# FPGA_misc.net
KiCad netlist of a schematic drawn in Altium Designer
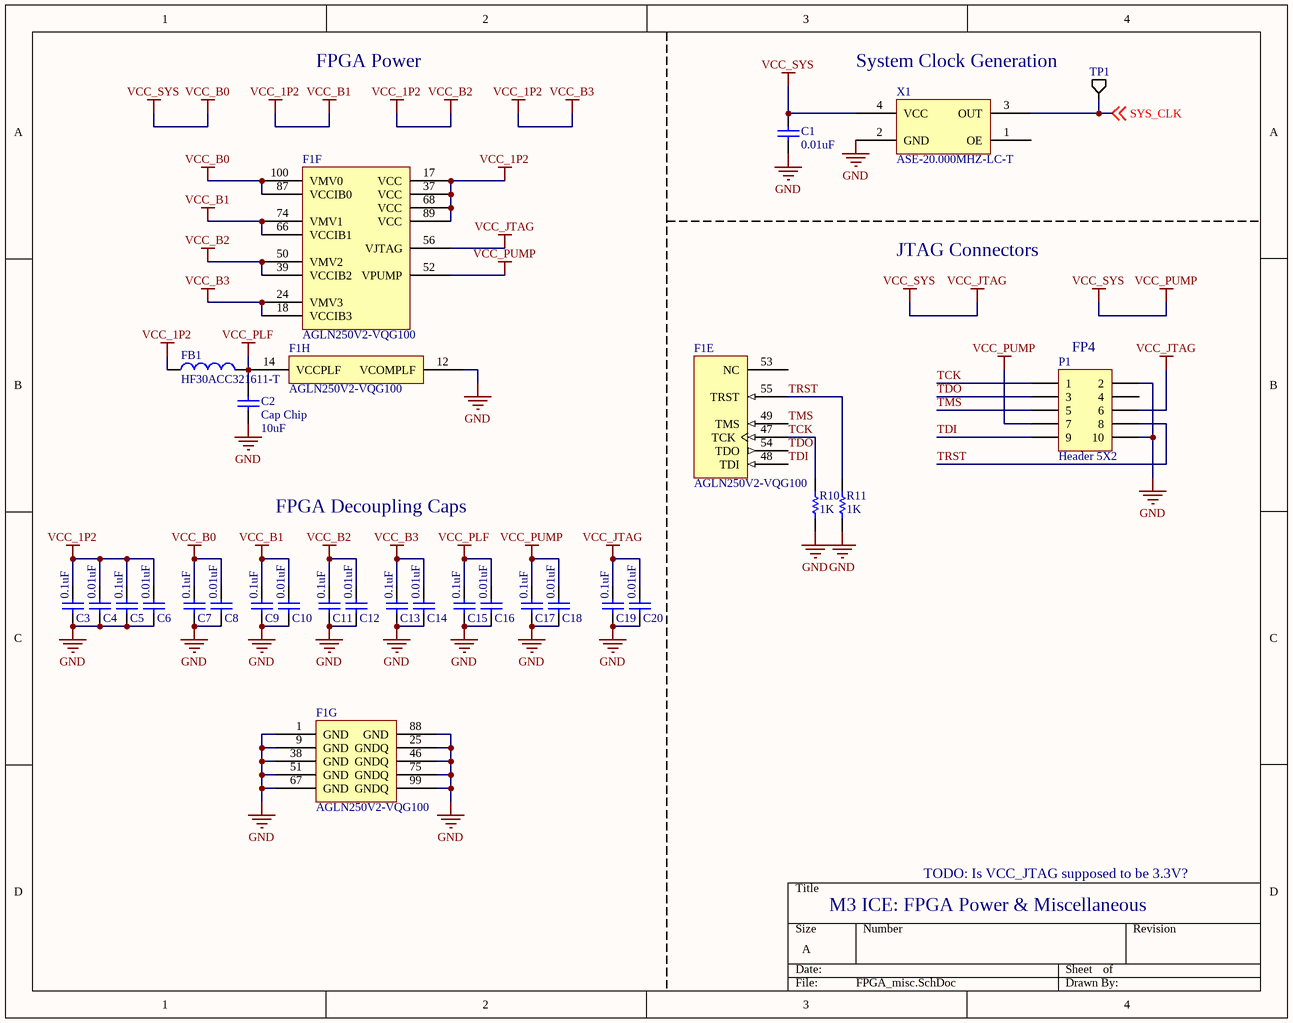
[diagram p0: FPGA_misc.SchDoc]

(export (version "E")
  (design (tool "Eeschema 10.0.6"))
  (components
    (comp (ref "C1")
      (value "0.01uF")
      (footprint "1608[0603]")
      (description "Capacitor (Semiconductor SIM Model)")
      (fields (field (name "Comment") "Cap Semi") (field (name "PUBLISHER") "Altium Limited"))
      (libsource (lib "Miscellaneous Devices") (part "Cap Semi"))
    )
    (comp (ref "C2")
      (value "Cap Chip")
      (footprint "0805")
      (description "Capacitor (Semiconductor SIM Model)")
      (fields (field (name "ALTIUM_VALUE") "10uF") (field (name "PUBLISHER") "Altium Limited"))
      (libsource (lib "M3") (part "Cap Chip"))
    )
    (comp (ref "C3")
      (value "0.1uF")
      (footprint "1608[0603]")
      (description "Capacitor (Semiconductor SIM Model)")
      (fields (field (name "Comment") "Cap Semi") (field (name "PUBLISHER") "Altium Limited"))
      (libsource (lib "Miscellaneous Devices") (part "Cap Semi"))
    )
    (comp (ref "C4")
      (value "0.01uF")
      (footprint "1608[0603]")
      (description "Capacitor (Semiconductor SIM Model)")
      (fields (field (name "Comment") "Cap Semi") (field (name "PUBLISHER") "Altium Limited"))
      (libsource (lib "Miscellaneous Devices") (part "Cap Semi"))
    )
    (comp (ref "C5")
      (value "0.1uF")
      (footprint "1608[0603]")
      (description "Capacitor (Semiconductor SIM Model)")
      (fields (field (name "Comment") "Cap Semi") (field (name "PUBLISHER") "Altium Limited"))
      (libsource (lib "Miscellaneous Devices") (part "Cap Semi"))
    )
    (comp (ref "C6")
      (value "0.01uF")
      (footprint "1608[0603]")
      (description "Capacitor (Semiconductor SIM Model)")
      (fields (field (name "Comment") "Cap Semi") (field (name "PUBLISHER") "Altium Limited"))
      (libsource (lib "Miscellaneous Devices") (part "Cap Semi"))
    )
    (comp (ref "C7")
      (value "0.1uF")
      (footprint "1608[0603]")
      (description "Capacitor (Semiconductor SIM Model)")
      (fields (field (name "Comment") "Cap Semi") (field (name "PUBLISHER") "Altium Limited"))
      (libsource (lib "Miscellaneous Devices") (part "Cap Semi"))
    )
    (comp (ref "C8")
      (value "0.01uF")
      (footprint "1608[0603]")
      (description "Capacitor (Semiconductor SIM Model)")
      (fields (field (name "Comment") "Cap Semi") (field (name "PUBLISHER") "Altium Limited"))
      (libsource (lib "Miscellaneous Devices") (part "Cap Semi"))
    )
    (comp (ref "C9")
      (value "0.1uF")
      (footprint "1608[0603]")
      (description "Capacitor (Semiconductor SIM Model)")
      (fields (field (name "Comment") "Cap Semi") (field (name "PUBLISHER") "Altium Limited"))
      (libsource (lib "Miscellaneous Devices") (part "Cap Semi"))
    )
    (comp (ref "C10")
      (value "0.01uF")
      (footprint "1608[0603]")
      (description "Capacitor (Semiconductor SIM Model)")
      (fields (field (name "Comment") "Cap Semi") (field (name "PUBLISHER") "Altium Limited"))
      (libsource (lib "Miscellaneous Devices") (part "Cap Semi"))
    )
    (comp (ref "C11")
      (value "0.1uF")
      (footprint "1608[0603]")
      (description "Capacitor (Semiconductor SIM Model)")
      (fields (field (name "Comment") "Cap Semi") (field (name "PUBLISHER") "Altium Limited"))
      (libsource (lib "Miscellaneous Devices") (part "Cap Semi"))
    )
    (comp (ref "C12")
      (value "0.01uF")
      (footprint "1608[0603]")
      (description "Capacitor (Semiconductor SIM Model)")
      (fields (field (name "Comment") "Cap Semi") (field (name "PUBLISHER") "Altium Limited"))
      (libsource (lib "Miscellaneous Devices") (part "Cap Semi"))
    )
    (comp (ref "C13")
      (value "0.1uF")
      (footprint "1608[0603]")
      (description "Capacitor (Semiconductor SIM Model)")
      (fields (field (name "Comment") "Cap Semi") (field (name "PUBLISHER") "Altium Limited"))
      (libsource (lib "Miscellaneous Devices") (part "Cap Semi"))
    )
    (comp (ref "C14")
      (value "0.01uF")
      (footprint "1608[0603]")
      (description "Capacitor (Semiconductor SIM Model)")
      (fields (field (name "Comment") "Cap Semi") (field (name "PUBLISHER") "Altium Limited"))
      (libsource (lib "Miscellaneous Devices") (part "Cap Semi"))
    )
    (comp (ref "C15")
      (value "0.1uF")
      (footprint "1608[0603]")
      (description "Capacitor (Semiconductor SIM Model)")
      (fields (field (name "Comment") "Cap Semi") (field (name "PUBLISHER") "Altium Limited"))
      (libsource (lib "Miscellaneous Devices") (part "Cap Semi"))
    )
    (comp (ref "C16")
      (value "0.01uF")
      (footprint "1608[0603]")
      (description "Capacitor (Semiconductor SIM Model)")
      (fields (field (name "Comment") "Cap Semi") (field (name "PUBLISHER") "Altium Limited"))
      (libsource (lib "Miscellaneous Devices") (part "Cap Semi"))
    )
    (comp (ref "C17")
      (value "0.1uF")
      (footprint "1608[0603]")
      (description "Capacitor (Semiconductor SIM Model)")
      (fields (field (name "Comment") "Cap Semi") (field (name "PUBLISHER") "Altium Limited"))
      (libsource (lib "Miscellaneous Devices") (part "Cap Semi"))
    )
    (comp (ref "C18")
      (value "0.01uF")
      (footprint "1608[0603]")
      (description "Capacitor (Semiconductor SIM Model)")
      (fields (field (name "Comment") "Cap Semi") (field (name "PUBLISHER") "Altium Limited"))
      (libsource (lib "Miscellaneous Devices") (part "Cap Semi"))
    )
    (comp (ref "C19")
      (value "0.1uF")
      (footprint "1608[0603]")
      (description "Capacitor (Semiconductor SIM Model)")
      (fields (field (name "Comment") "Cap Semi") (field (name "PUBLISHER") "Altium Limited"))
      (libsource (lib "Miscellaneous Devices") (part "Cap Semi"))
    )
    (comp (ref "C20")
      (value "0.01uF")
      (footprint "1608[0603]")
      (description "Capacitor (Semiconductor SIM Model)")
      (fields (field (name "Comment") "Cap Semi") (field (name "PUBLISHER") "Altium Limited"))
      (libsource (lib "Miscellaneous Devices") (part "Cap Semi"))
    )
    (comp (ref "F1")
      (value "AGLN250V2-VQG100")
      (footprint "VQ100_N")
      (fields (field (name "PUBLISHER") "Altium Limited"))
      (libsource (lib "Actel IGLOO nano") (part "AGLN250V2-VQG100"))
    )
    (comp (ref "FB1")
      (value "HF30ACC321611-T")
      (footprint "Ferrite_Bead_3.2mm_1.6mm")
      (libsource (lib "M3") (part "Ferrite Bead HF30ACC321611-T"))
    )
    (comp (ref "P1")
      (value "Header 5X2")
      (footprint "HDR2X5")
      (description "Header, 5-Pin, Dual row")
      (fields (field (name "PUBLISHER") "Altium Limited"))
      (libsource (lib "Miscellaneous Connectors") (part "Header 5X2"))
    )
    (comp (ref "R10")
      (value "1K")
      (footprint "0603")
      (description "Semiconductor Resistor")
      (fields (field (name "Comment") "Res Chip") (field (name "PUBLISHER") "Altium Limited"))
      (libsource (lib "M3") (part "Res Chip"))
    )
    (comp (ref "R11")
      (value "1K")
      (footprint "0603")
      (description "Semiconductor Resistor")
      (fields (field (name "Comment") "Res Chip") (field (name "PUBLISHER") "Altium Limited"))
      (libsource (lib "M3") (part "Res Chip"))
    )
    (comp (ref "TP1") (value "TP") (footprint "TP") (libsource (lib "M3") (part "TP")))
    (comp (ref "X1")
      (value "ASE-20.000MHZ-LC-T")
      (footprint "CRYSTAL_3.2mm_2.5mm")
      (libsource (lib "M3") (part "ASE-20.000MHZ-LC-T"))
    )
  )
  (nets
    (net (code "1") (name "/TCK") (class "Default")
      (node (ref "F1") (pin "47") (pinfunction "TCK_47") (pintype "input"))
      (node (ref "P1") (pin "1") (pinfunction "1_1") (pintype "passive"))
      (node (ref "R10") (pin "1") (pinfunction "1_1") (pintype "passive"))
    )
    (net (code "2") (name "/TDI") (class "Default")
      (node (ref "F1") (pin "48") (pinfunction "TDI_48") (pintype "input"))
      (node (ref "P1") (pin "9") (pinfunction "9_9") (pintype "passive"))
    )
    (net (code "3") (name "/TDO") (class "Default")
      (node (ref "F1") (pin "54") (pinfunction "TDO_54") (pintype "output"))
      (node (ref "P1") (pin "3") (pinfunction "3_3") (pintype "passive"))
    )
    (net (code "4") (name "/TMS") (class "Default")
      (node (ref "F1") (pin "49") (pinfunction "TMS_49") (pintype "input"))
      (node (ref "P1") (pin "5") (pinfunction "5_5") (pintype "passive"))
    )
    (net (code "5") (name "/TRST") (class "Default")
      (node (ref "F1") (pin "55") (pinfunction "TRST_55") (pintype "input"))
      (node (ref "P1") (pin "8") (pinfunction "8_8") (pintype "passive"))
      (node (ref "R11") (pin "1") (pinfunction "1_1") (pintype "passive"))
    )
    (net (code "6") (name "GND") (class "Default")
      (node (ref "C1") (pin "1") (pinfunction "1_1") (pintype "passive"))
      (node (ref "C10") (pin "1") (pinfunction "1_1") (pintype "passive"))
      (node (ref "C11") (pin "1") (pinfunction "1_1") (pintype "passive"))
      (node (ref "C12") (pin "1") (pinfunction "1_1") (pintype "passive"))
      (node (ref "C13") (pin "1") (pinfunction "1_1") (pintype "passive"))
      (node (ref "C14") (pin "1") (pinfunction "1_1") (pintype "passive"))
      (node (ref "C15") (pin "1") (pinfunction "1_1") (pintype "passive"))
      (node (ref "C16") (pin "1") (pinfunction "1_1") (pintype "passive"))
      (node (ref "C17") (pin "1") (pinfunction "1_1") (pintype "passive"))
      (node (ref "C18") (pin "1") (pinfunction "1_1") (pintype "passive"))
      (node (ref "C19") (pin "1") (pinfunction "1_1") (pintype "passive"))
      (node (ref "C2") (pin "1") (pinfunction "1_1") (pintype "passive"))
      (node (ref "C20") (pin "1") (pinfunction "1_1") (pintype "passive"))
      (node (ref "C3") (pin "1") (pinfunction "1_1") (pintype "passive"))
      (node (ref "C4") (pin "1") (pinfunction "1_1") (pintype "passive"))
      (node (ref "C5") (pin "1") (pinfunction "1_1") (pintype "passive"))
      (node (ref "C6") (pin "1") (pinfunction "1_1") (pintype "passive"))
      (node (ref "C7") (pin "1") (pinfunction "1_1") (pintype "passive"))
      (node (ref "C8") (pin "1") (pinfunction "1_1") (pintype "passive"))
      (node (ref "C9") (pin "1") (pinfunction "1_1") (pintype "passive"))
      (node (ref "F1") (pin "1") (pinfunction "GND_1") (pintype "power_in"))
      (node (ref "F1") (pin "12") (pinfunction "VCOMPLF_12") (pintype "power_in"))
      (node (ref "F1") (pin "25") (pinfunction "GNDQ_25") (pintype "power_in"))
      (node (ref "F1") (pin "38") (pinfunction "GND_38") (pintype "power_in"))
      (node (ref "F1") (pin "46") (pinfunction "GNDQ_46") (pintype "power_in"))
      (node (ref "F1") (pin "51") (pinfunction "GND_51") (pintype "power_in"))
      (node (ref "F1") (pin "67") (pinfunction "GND_67") (pintype "power_in"))
      (node (ref "F1") (pin "75") (pinfunction "GNDQ_75") (pintype "power_in"))
      (node (ref "F1") (pin "88") (pinfunction "GND_88") (pintype "power_in"))
      (node (ref "F1") (pin "9") (pinfunction "GND_9") (pintype "power_in"))
      (node (ref "F1") (pin "99") (pinfunction "GNDQ_99") (pintype "power_in"))
      (node (ref "P1") (pin "10") (pinfunction "10_10") (pintype "passive"))
      (node (ref "P1") (pin "2") (pinfunction "2_2") (pintype "passive"))
      (node (ref "R10") (pin "2") (pinfunction "2_2") (pintype "passive"))
      (node (ref "R11") (pin "2") (pinfunction "2_2") (pintype "passive"))
      (node (ref "X1") (pin "2") (pinfunction "GND_2") (pintype "passive"))
    )
    (net (code "7") (name "SYS_CLK") (class "Default")
      (node (ref "TP1") (pin "1") (pinfunction "A_1") (pintype "passive"))
      (node (ref "X1") (pin "3") (pinfunction "OUT_3") (pintype "passive"))
    )
    (net (code "8") (name "VCC_1P2") (class "Default")
      (node (ref "C10") (pin "2") (pinfunction "2_2") (pintype "passive"))
      (node (ref "C11") (pin "2") (pinfunction "2_2") (pintype "passive"))
      (node (ref "C12") (pin "2") (pinfunction "2_2") (pintype "passive"))
      (node (ref "C13") (pin "2") (pinfunction "2_2") (pintype "passive"))
      (node (ref "C14") (pin "2") (pinfunction "2_2") (pintype "passive"))
      (node (ref "C3") (pin "2") (pinfunction "2_2") (pintype "passive"))
      (node (ref "C4") (pin "2") (pinfunction "2_2") (pintype "passive"))
      (node (ref "C5") (pin "2") (pinfunction "2_2") (pintype "passive"))
      (node (ref "C6") (pin "2") (pinfunction "2_2") (pintype "passive"))
      (node (ref "C9") (pin "2") (pinfunction "2_2") (pintype "passive"))
      (node (ref "F1") (pin "17") (pinfunction "VCC_17") (pintype "power_in"))
      (node (ref "F1") (pin "18") (pinfunction "VCCIB3_18") (pintype "power_in"))
      (node (ref "F1") (pin "24") (pinfunction "VMV3_24") (pintype "power_in"))
      (node (ref "F1") (pin "37") (pinfunction "VCC_37") (pintype "power_in"))
      (node (ref "F1") (pin "39") (pinfunction "VCCIB2_39") (pintype "power_in"))
      (node (ref "F1") (pin "50") (pinfunction "VMV2_50") (pintype "power_in"))
      (node (ref "F1") (pin "66") (pinfunction "VCCIB1_66") (pintype "power_in"))
      (node (ref "F1") (pin "68") (pinfunction "VCC_68") (pintype "power_in"))
      (node (ref "F1") (pin "74") (pinfunction "VMV1_74") (pintype "power_in"))
      (node (ref "F1") (pin "89") (pinfunction "VCC_89") (pintype "power_in"))
      (node (ref "FB1") (pin "1") (pinfunction "1_1") (pintype "passive"))
    )
    (net (code "9") (name "VCC_B0") (class "Default")
      (node (ref "C1") (pin "2") (pinfunction "2_2") (pintype "passive"))
      (node (ref "C17") (pin "2") (pinfunction "2_2") (pintype "passive"))
      (node (ref "C18") (pin "2") (pinfunction "2_2") (pintype "passive"))
      (node (ref "C19") (pin "2") (pinfunction "2_2") (pintype "passive"))
      (node (ref "C20") (pin "2") (pinfunction "2_2") (pintype "passive"))
      (node (ref "C7") (pin "2") (pinfunction "2_2") (pintype "passive"))
      (node (ref "C8") (pin "2") (pinfunction "2_2") (pintype "passive"))
      (node (ref "F1") (pin "100") (pinfunction "VMV0_100") (pintype "power_in"))
      (node (ref "F1") (pin "52") (pinfunction "VPUMP_52") (pintype "power_in"))
      (node (ref "F1") (pin "56") (pinfunction "VJTAG_56") (pintype "power_in"))
      (node (ref "F1") (pin "87") (pinfunction "VCCIB0_87") (pintype "power_in"))
      (node (ref "P1") (pin "6") (pinfunction "6_6") (pintype "passive"))
      (node (ref "P1") (pin "7") (pinfunction "7_7") (pintype "passive"))
      (node (ref "X1") (pin "4") (pinfunction "VCC_4") (pintype "passive"))
    )
    (net (code "10") (name "VCC_PLF") (class "Default")
      (node (ref "C15") (pin "2") (pinfunction "2_2") (pintype "passive"))
      (node (ref "C16") (pin "2") (pinfunction "2_2") (pintype "passive"))
      (node (ref "C2") (pin "2") (pinfunction "2_2") (pintype "passive"))
      (node (ref "F1") (pin "14") (pinfunction "VCCPLF_14") (pintype "power_in"))
      (node (ref "FB1") (pin "2") (pinfunction "2_2") (pintype "passive"))
    )
    (net (code "11") (name "unconnected-(F1E-NC-Pad53)") (class "Default")
      (node (ref "F1") (pin "53") (pinfunction "NC_53") (pintype "passive"))
    )
    (net (code "12") (name "unconnected-(P1-Pad4)") (class "Default")
      (node (ref "P1") (pin "4") (pinfunction "4_4") (pintype "passive"))
    )
    (net (code "13") (name "unconnected-(X1-OE-Pad1)") (class "Default")
      (node (ref "X1") (pin "1") (pinfunction "OE_1") (pintype "passive"))
    )
  )
)
